# MotionDetectorProgJIG.net
KiCad netlist of a schematic drawn in Altium Designer
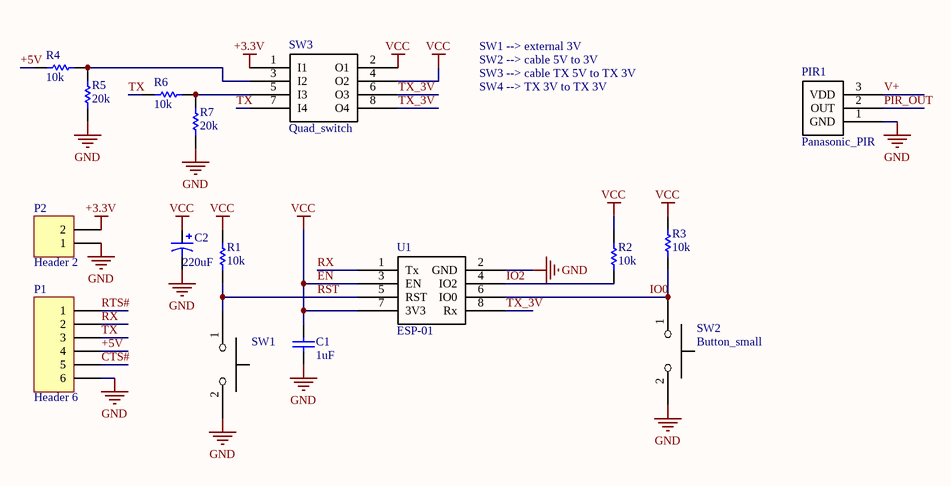
[diagram p0: MotionDetectorProgJIG.SchDoc]

(export (version "E")
  (design (tool "Eeschema 10.0.6"))
  (components
    (comp (ref "C1")
      (value "1uF")
      (footprint "RAD-0.3")
      (description "Capacitor")
      (fields (field (name "Comment") "Cap") (field (name "PUBLISHER") "Altium Limited"))
      (libsource (lib "Miscellaneous Devices") (part "Cap"))
    )
    (comp (ref "C2")
      (value "220uF")
      (footprint "RB7.6-15")
      (description "Polarized Capacitor (Radial)")
      (fields (field (name "Comment") "Cap Pol1") (field (name "PUBLISHER") "Altium Limited"))
      (libsource (lib "Miscellaneous Devices") (part "Cap Pol1"))
    )
    (comp (ref "P1")
      (value "Header 6")
      (footprint "HDR1X6")
      (description "Header, 6-Pin")
      (fields (field (name "PUBLISHER") "Altium Limited"))
      (libsource (lib "Miscellaneous Connectors") (part "Header 6"))
    )
    (comp (ref "P2")
      (value "Header 2")
      (footprint "HDR1X2")
      (description "Header, 2-Pin")
      (fields (field (name "PUBLISHER") "Altium Limited"))
      (libsource (lib "Miscellaneous Connectors") (part "Header 2"))
    )
    (comp (ref "PIR1")
      (value "Panasonic_PIR")
      (footprint "Panasonic_PIR")
      (libsource (lib "MotionDetectorSchematicLib") (part "Panasonic_PIR"))
    )
    (comp (ref "R1")
      (value "10k")
      (footprint "AXIAL-0.3")
      (description "Resistor")
      (fields (field (name "Comment") "Res1") (field (name "PUBLISHER") "Altium Limited"))
      (libsource (lib "Miscellaneous Devices") (part "Res1"))
    )
    (comp (ref "R2")
      (value "10k")
      (footprint "AXIAL-0.3")
      (description "Resistor")
      (fields (field (name "Comment") "Res1") (field (name "PUBLISHER") "Altium Limited"))
      (libsource (lib "Miscellaneous Devices") (part "Res1"))
    )
    (comp (ref "R3")
      (value "10k")
      (footprint "AXIAL-0.3")
      (description "Resistor")
      (fields (field (name "Comment") "Res1") (field (name "PUBLISHER") "Altium Limited"))
      (libsource (lib "Miscellaneous Devices") (part "Res1"))
    )
    (comp (ref "R4")
      (value "10k")
      (footprint "AXIAL-0.3")
      (description "Resistor")
      (fields (field (name "Comment") "Res1") (field (name "PUBLISHER") "Altium Limited"))
      (libsource (lib "Miscellaneous Devices") (part "Res1"))
    )
    (comp (ref "R5")
      (value "20k")
      (footprint "AXIAL-0.3")
      (description "Resistor")
      (fields (field (name "Comment") "Res1") (field (name "PUBLISHER") "Altium Limited"))
      (libsource (lib "Miscellaneous Devices") (part "Res1"))
    )
    (comp (ref "R6")
      (value "10k")
      (footprint "AXIAL-0.3")
      (description "Resistor")
      (fields (field (name "Comment") "Res1") (field (name "PUBLISHER") "Altium Limited"))
      (libsource (lib "Miscellaneous Devices") (part "Res1"))
    )
    (comp (ref "R7")
      (value "20k")
      (footprint "AXIAL-0.3")
      (description "Resistor")
      (fields (field (name "Comment") "Res1") (field (name "PUBLISHER") "Altium Limited"))
      (libsource (lib "Miscellaneous Devices") (part "Res1"))
    )
    (comp (ref "SW1")
      (value "Button_small")
      (libsource (lib "MotionDetectorSchematicLib") (part "Button_small"))
    )
    (comp (ref "SW2")
      (value "Button_small")
      (libsource (lib "MotionDetectorSchematicLib") (part "Button_small"))
    )
    (comp (ref "SW3")
      (value "Quad_switch")
      (libsource (lib "MotionDetectorSchematicLib") (part "Quad_switch"))
    )
    (comp (ref "U1")
      (value "ESP-01")
      (footprint "ESP-01")
      (libsource (lib "MotionDetectorSchematicLib") (part "ESP-01"))
    )
  )
  (nets
    (net (code "1") (name "+3.3V") (class "Default")
      (node (ref "P2") (pin "2") (pinfunction "2_2") (pintype "passive"))
      (node (ref "SW3") (pin "1") (pinfunction "I1_1") (pintype "passive"))
    )
    (net (code "2") (name "/+5V") (class "Default")
      (node (ref "P1") (pin "4") (pinfunction "4_4") (pintype "passive"))
      (node (ref "R4") (pin "2") (pinfunction "2_2") (pintype "passive"))
    )
    (net (code "3") (name "/CTS#") (class "Default")
      (node (ref "P1") (pin "5") (pinfunction "5_5") (pintype "passive"))
    )
    (net (code "4") (name "/IO0") (class "Default")
      (node (ref "R3") (pin "1") (pinfunction "1_1") (pintype "passive"))
      (node (ref "SW2") (pin "1") (pintype "passive"))
      (node (ref "U1") (pin "6") (pinfunction "IO0_6") (pintype "passive"))
    )
    (net (code "5") (name "/IO2") (class "Default")
      (node (ref "R2") (pin "1") (pinfunction "1_1") (pintype "passive"))
      (node (ref "U1") (pin "4") (pinfunction "IO2_4") (pintype "passive"))
    )
    (net (code "6") (name "/PIR_OUT") (class "Default")
      (node (ref "PIR1") (pin "2") (pinfunction "OUT_2") (pintype "passive"))
    )
    (net (code "7") (name "/RST") (class "Default")
      (node (ref "R1") (pin "1") (pinfunction "1_1") (pintype "passive"))
      (node (ref "SW1") (pin "1") (pintype "passive"))
      (node (ref "U1") (pin "5") (pinfunction "RST_5") (pintype "passive"))
    )
    (net (code "8") (name "/RTS#") (class "Default")
      (node (ref "P1") (pin "1") (pinfunction "1_1") (pintype "passive"))
    )
    (net (code "9") (name "/RX") (class "Default")
      (node (ref "P1") (pin "2") (pinfunction "2_2") (pintype "passive"))
      (node (ref "U1") (pin "1") (pinfunction "Tx_1") (pintype "passive"))
    )
    (net (code "10") (name "/TX") (class "Default")
      (node (ref "P1") (pin "3") (pinfunction "3_3") (pintype "passive"))
      (node (ref "R6") (pin "2") (pinfunction "2_2") (pintype "passive"))
      (node (ref "SW3") (pin "7") (pinfunction "I4_7") (pintype "passive"))
    )
    (net (code "11") (name "/TX_3V") (class "Default")
      (node (ref "SW3") (pin "6") (pinfunction "O3_6") (pintype "passive"))
      (node (ref "SW3") (pin "8") (pinfunction "O4_8") (pintype "passive"))
      (node (ref "U1") (pin "8") (pinfunction "Rx_8") (pintype "passive"))
    )
    (net (code "12") (name "/V+") (class "Default")
      (node (ref "PIR1") (pin "3") (pinfunction "VDD_3") (pintype "passive"))
    )
    (net (code "13") (name "GND") (class "Default")
      (node (ref "C1") (pin "2") (pinfunction "2_2") (pintype "passive"))
      (node (ref "C2") (pin "2") (pinfunction "2_2") (pintype "passive"))
      (node (ref "P1") (pin "6") (pinfunction "6_6") (pintype "passive"))
      (node (ref "P2") (pin "1") (pinfunction "1_1") (pintype "passive"))
      (node (ref "PIR1") (pin "1") (pinfunction "GND_1") (pintype "passive"))
      (node (ref "R5") (pin "2") (pinfunction "2_2") (pintype "passive"))
      (node (ref "R7") (pin "2") (pinfunction "2_2") (pintype "passive"))
      (node (ref "SW1") (pin "2") (pintype "passive"))
      (node (ref "SW2") (pin "2") (pintype "passive"))
      (node (ref "U1") (pin "2") (pinfunction "GND_2") (pintype "passive"))
    )
    (net (code "14") (name "Net-(SW3-I2)") (class "Default")
      (node (ref "R4") (pin "1") (pinfunction "1_1") (pintype "passive"))
      (node (ref "R5") (pin "1") (pinfunction "1_1") (pintype "passive"))
      (node (ref "SW3") (pin "3") (pinfunction "I2_3") (pintype "passive"))
    )
    (net (code "15") (name "Net-(SW3-I3)") (class "Default")
      (node (ref "R6") (pin "1") (pinfunction "1_1") (pintype "passive"))
      (node (ref "R7") (pin "1") (pinfunction "1_1") (pintype "passive"))
      (node (ref "SW3") (pin "5") (pinfunction "I3_5") (pintype "passive"))
    )
    (net (code "16") (name "VCC") (class "Default")
      (node (ref "C1") (pin "1") (pinfunction "1_1") (pintype "passive"))
      (node (ref "C2") (pin "1") (pinfunction "1_1") (pintype "passive"))
      (node (ref "R1") (pin "2") (pinfunction "2_2") (pintype "passive"))
      (node (ref "R2") (pin "2") (pinfunction "2_2") (pintype "passive"))
      (node (ref "R3") (pin "2") (pinfunction "2_2") (pintype "passive"))
      (node (ref "SW3") (pin "2") (pinfunction "O1_2") (pintype "passive"))
      (node (ref "SW3") (pin "4") (pinfunction "O2_4") (pintype "passive"))
      (node (ref "U1") (pin "3") (pinfunction "EN_3") (pintype "passive"))
      (node (ref "U1") (pin "7") (pinfunction "3V3_7") (pintype "passive"))
    )
  )
)
